# MI.net
KiCad netlist of a schematic drawn in Altium Designer
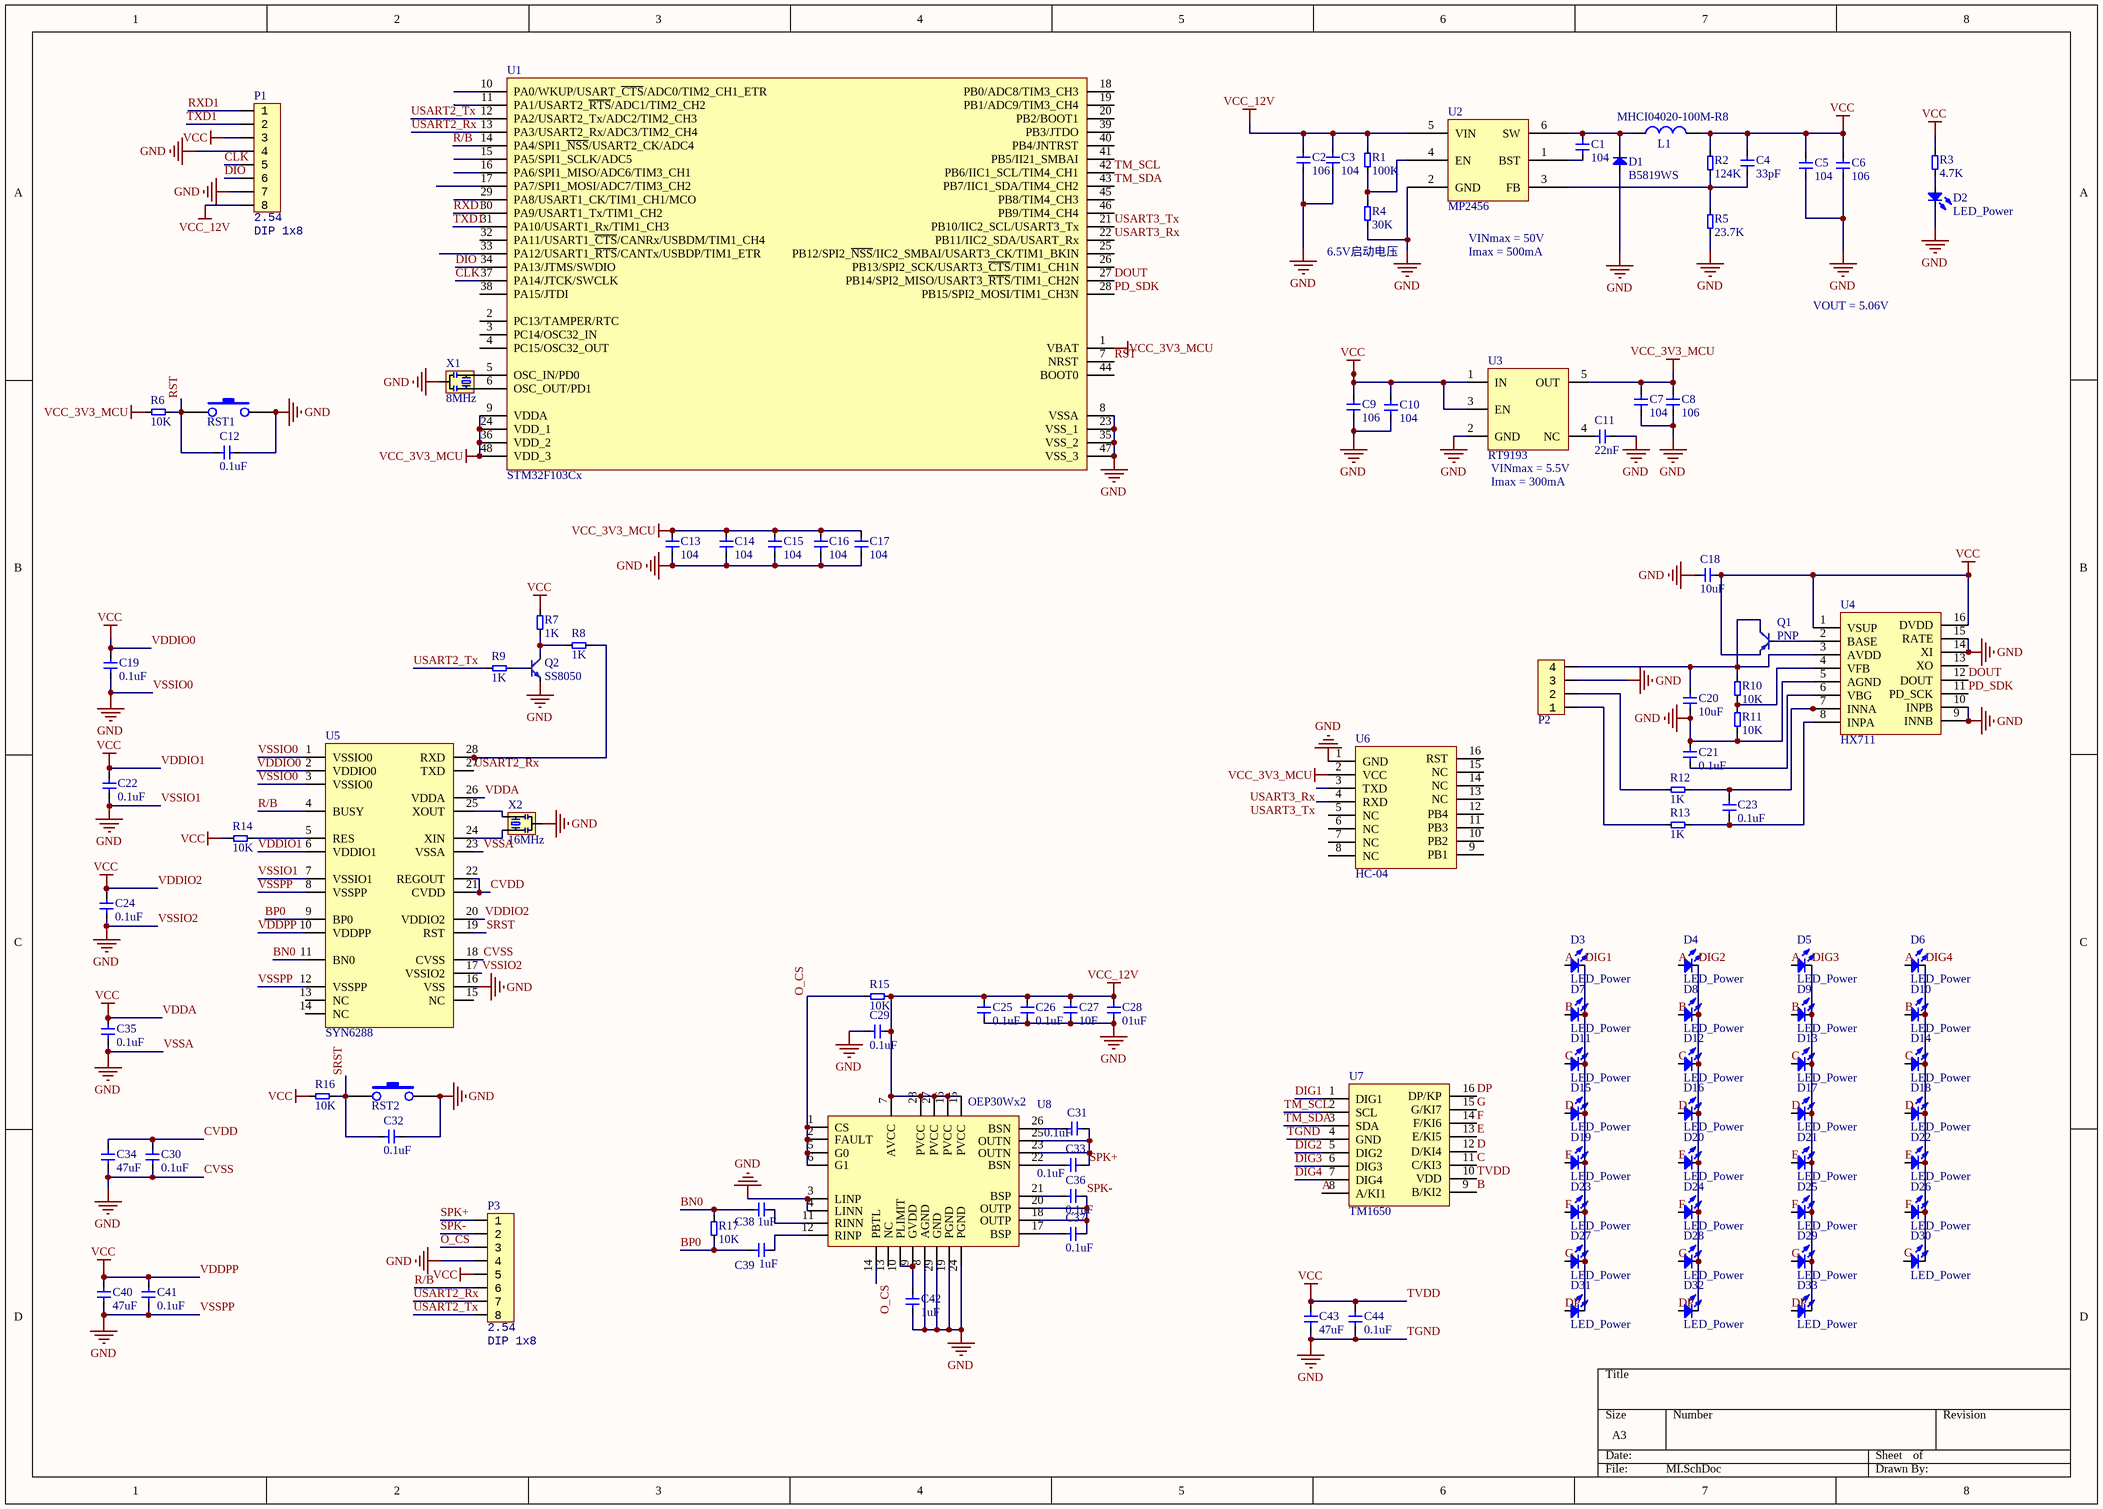
[diagram p0: MI.SchDoc]

(export (version "E")
  (design (tool "Eeschema 10.0.6"))
  (components
    (comp (ref "C1") (value "104") (footprint "CAP-0603-L") (libsource (lib "Hare_Library") (part "CAP")))
    (comp (ref "C2") (value "106") (footprint "CAP-0603-L") (libsource (lib "Hare_Library") (part "CAP")))
    (comp (ref "C3") (value "104") (footprint "CAP-0603-L") (libsource (lib "Hare_Library") (part "CAP")))
    (comp (ref "C4") (value "33pF") (footprint "CAP-0603-L") (libsource (lib "Hare_Library") (part "CAP")))
    (comp (ref "C5") (value "104") (footprint "CAP-0603-L") (libsource (lib "Hare_Library") (part "CAP")))
    (comp (ref "C6") (value "106") (footprint "CAP-0603-L") (libsource (lib "Hare_Library") (part "CAP")))
    (comp (ref "C7") (value "104") (footprint "CAP-0603-L") (libsource (lib "Hare_Library") (part "CAP")))
    (comp (ref "C8") (value "106") (footprint "CAP-0603-L") (libsource (lib "Hare_Library") (part "CAP")))
    (comp (ref "C9") (value "106") (footprint "CAP-0603-L") (libsource (lib "Hare_Library") (part "CAP")))
    (comp (ref "C10") (value "104") (footprint "CAP-0603-L") (libsource (lib "Hare_Library") (part "CAP")))
    (comp (ref "C11") (value "22nF") (footprint "CAP-0603-L") (libsource (lib "Hare_Library") (part "CAP")))
    (comp (ref "C12")
      (value "0.1uF")
      (footprint "CAP-0603-L")
      (libsource (lib "DaqoLib_Devices") (part "CAP"))
    )
    (comp (ref "C13") (value "104") (footprint "CAP-0603-L") (libsource (lib "DaqoLib_Devices") (part "CAP")))
    (comp (ref "C14") (value "104") (footprint "CAP-0603-L") (libsource (lib "DaqoLib_Devices") (part "CAP")))
    (comp (ref "C15") (value "104") (footprint "CAP-0603-L") (libsource (lib "DaqoLib_Devices") (part "CAP")))
    (comp (ref "C16") (value "104") (footprint "CAP-0603-L") (libsource (lib "DaqoLib_Devices") (part "CAP")))
    (comp (ref "C17") (value "104") (footprint "CAP-0603-L") (libsource (lib "DaqoLib_Devices") (part "CAP")))
    (comp (ref "C18")
      (value "10uF")
      (footprint "CAP-0603-L")
      (libsource (lib "DaqoLib_Devices") (part "CAP"))
    )
    (comp (ref "C19")
      (value "0.1uF")
      (footprint "CAP-0603-L")
      (libsource (lib "DaqoLib_Devices") (part "CAP"))
    )
    (comp (ref "C20")
      (value "10uF")
      (footprint "CAP-0603-L")
      (libsource (lib "DaqoLib_Devices") (part "CAP"))
    )
    (comp (ref "C21")
      (value "0.1uF")
      (footprint "CAP-0603-L")
      (libsource (lib "DaqoLib_Devices") (part "CAP"))
    )
    (comp (ref "C22")
      (value "0.1uF")
      (footprint "CAP-0603-L")
      (libsource (lib "DaqoLib_Devices") (part "CAP"))
    )
    (comp (ref "C23")
      (value "0.1uF")
      (footprint "CAP-0603-L")
      (libsource (lib "DaqoLib_Devices") (part "CAP"))
    )
    (comp (ref "C24")
      (value "0.1uF")
      (footprint "CAP-0603-L")
      (libsource (lib "DaqoLib_Devices") (part "CAP"))
    )
    (comp (ref "C25")
      (value "0.1uF")
      (footprint "CAP-0603-L")
      (libsource (lib "DaqoLib_Devices") (part "CAP"))
    )
    (comp (ref "C26")
      (value "0.1uF")
      (footprint "CAP-0603-L")
      (libsource (lib "DaqoLib_Devices") (part "CAP"))
    )
    (comp (ref "C27") (value "10F") (footprint "CAP-0603-L") (libsource (lib "DaqoLib_Devices") (part "CAP")))
    (comp (ref "C28")
      (value "01uF")
      (footprint "CAP-0603-L")
      (libsource (lib "DaqoLib_Devices") (part "CAP"))
    )
    (comp (ref "C29")
      (value "0.1uF")
      (footprint "CAP-0603-L")
      (libsource (lib "DaqoLib_Devices") (part "CAP"))
    )
    (comp (ref "C30")
      (value "0.1uF")
      (footprint "CAP-0603-L")
      (libsource (lib "DaqoLib_Devices") (part "CAP"))
    )
    (comp (ref "C31")
      (value "0.1uF")
      (footprint "CAP-0603-L")
      (libsource (lib "DaqoLib_Devices") (part "CAP"))
    )
    (comp (ref "C32")
      (value "0.1uF")
      (footprint "CAP-0603-L")
      (libsource (lib "DaqoLib_Devices") (part "CAP"))
    )
    (comp (ref "C33")
      (value "0.1uF")
      (footprint "CAP-0603-L")
      (libsource (lib "DaqoLib_Devices") (part "CAP"))
    )
    (comp (ref "C34")
      (value "47uF")
      (footprint "CAP-0603-L")
      (libsource (lib "DaqoLib_Devices") (part "CAP"))
    )
    (comp (ref "C35")
      (value "0.1uF")
      (footprint "CAP-0603-L")
      (libsource (lib "DaqoLib_Devices") (part "CAP"))
    )
    (comp (ref "C36")
      (value "0.1uF")
      (footprint "CAP-0603-L")
      (libsource (lib "DaqoLib_Devices") (part "CAP"))
    )
    (comp (ref "C37")
      (value "0.1uF")
      (footprint "CAP-0603-L")
      (libsource (lib "DaqoLib_Devices") (part "CAP"))
    )
    (comp (ref "C38") (value "1uF") (footprint "CAP-0603-L") (libsource (lib "DaqoLib_Devices") (part "CAP")))
    (comp (ref "C39") (value "1uF") (footprint "CAP-0603-L") (libsource (lib "DaqoLib_Devices") (part "CAP")))
    (comp (ref "C40")
      (value "47uF")
      (footprint "CAP-0603-L")
      (libsource (lib "DaqoLib_Devices") (part "CAP"))
    )
    (comp (ref "C41")
      (value "0.1uF")
      (footprint "CAP-0603-L")
      (libsource (lib "DaqoLib_Devices") (part "CAP"))
    )
    (comp (ref "C42") (value "1uF") (footprint "CAP-0603-L") (libsource (lib "DaqoLib_Devices") (part "CAP")))
    (comp (ref "C43")
      (value "47uF")
      (footprint "CAP-0603-L")
      (libsource (lib "DaqoLib_Devices") (part "CAP"))
    )
    (comp (ref "C44")
      (value "0.1uF")
      (footprint "CAP-0603-L")
      (libsource (lib "DaqoLib_Devices") (part "CAP"))
    )
    (comp (ref "D1") (value "B5819WS") (footprint "SOD_323") (libsource (lib "Hare_Library") (part "Diode")))
    (comp (ref "D2")
      (value "LED_Power")
      (footprint "LED_0603-L")
      (libsource (lib "Hare_Library") (part "LED"))
    )
    (comp (ref "D3")
      (value "LED_Power")
      (footprint "LED_0603-L")
      (libsource (lib "Hare_Library") (part "LED"))
    )
    (comp (ref "D4")
      (value "LED_Power")
      (footprint "LED_0603-L")
      (libsource (lib "Hare_Library") (part "LED"))
    )
    (comp (ref "D5")
      (value "LED_Power")
      (footprint "LED_0603-L")
      (libsource (lib "Hare_Library") (part "LED"))
    )
    (comp (ref "D6")
      (value "LED_Power")
      (footprint "LED_0603-L")
      (libsource (lib "Hare_Library") (part "LED"))
    )
    (comp (ref "D7")
      (value "LED_Power")
      (footprint "LED_0603-L")
      (libsource (lib "Hare_Library") (part "LED"))
    )
    (comp (ref "D8")
      (value "LED_Power")
      (footprint "LED_0603-L")
      (libsource (lib "Hare_Library") (part "LED"))
    )
    (comp (ref "D9")
      (value "LED_Power")
      (footprint "LED_0603-L")
      (libsource (lib "Hare_Library") (part "LED"))
    )
    (comp (ref "D10")
      (value "LED_Power")
      (footprint "LED_0603-L")
      (libsource (lib "Hare_Library") (part "LED"))
    )
    (comp (ref "D11")
      (value "LED_Power")
      (footprint "LED_0603-L")
      (libsource (lib "Hare_Library") (part "LED"))
    )
    (comp (ref "D12")
      (value "LED_Power")
      (footprint "LED_0603-L")
      (libsource (lib "Hare_Library") (part "LED"))
    )
    (comp (ref "D13")
      (value "LED_Power")
      (footprint "LED_0603-L")
      (libsource (lib "Hare_Library") (part "LED"))
    )
    (comp (ref "D14")
      (value "LED_Power")
      (footprint "LED_0603-L")
      (libsource (lib "Hare_Library") (part "LED"))
    )
    (comp (ref "D15")
      (value "LED_Power")
      (footprint "LED_0603-L")
      (libsource (lib "Hare_Library") (part "LED"))
    )
    (comp (ref "D16")
      (value "LED_Power")
      (footprint "LED_0603-L")
      (libsource (lib "Hare_Library") (part "LED"))
    )
    (comp (ref "D17")
      (value "LED_Power")
      (footprint "LED_0603-L")
      (libsource (lib "Hare_Library") (part "LED"))
    )
    (comp (ref "D18")
      (value "LED_Power")
      (footprint "LED_0603-L")
      (libsource (lib "Hare_Library") (part "LED"))
    )
    (comp (ref "D19")
      (value "LED_Power")
      (footprint "LED_0603-L")
      (libsource (lib "Hare_Library") (part "LED"))
    )
    (comp (ref "D20")
      (value "LED_Power")
      (footprint "LED_0603-L")
      (libsource (lib "Hare_Library") (part "LED"))
    )
    (comp (ref "D21")
      (value "LED_Power")
      (footprint "LED_0603-L")
      (libsource (lib "Hare_Library") (part "LED"))
    )
    (comp (ref "D22")
      (value "LED_Power")
      (footprint "LED_0603-L")
      (libsource (lib "Hare_Library") (part "LED"))
    )
    (comp (ref "D23")
      (value "LED_Power")
      (footprint "LED_0603-L")
      (libsource (lib "Hare_Library") (part "LED"))
    )
    (comp (ref "D24")
      (value "LED_Power")
      (footprint "LED_0603-L")
      (libsource (lib "Hare_Library") (part "LED"))
    )
    (comp (ref "D25")
      (value "LED_Power")
      (footprint "LED_0603-L")
      (libsource (lib "Hare_Library") (part "LED"))
    )
    (comp (ref "D26")
      (value "LED_Power")
      (footprint "LED_0603-L")
      (libsource (lib "Hare_Library") (part "LED"))
    )
    (comp (ref "D27")
      (value "LED_Power")
      (footprint "LED_0603-L")
      (libsource (lib "Hare_Library") (part "LED"))
    )
    (comp (ref "D28")
      (value "LED_Power")
      (footprint "LED_0603-L")
      (libsource (lib "Hare_Library") (part "LED"))
    )
    (comp (ref "D29")
      (value "LED_Power")
      (footprint "LED_0603-L")
      (libsource (lib "Hare_Library") (part "LED"))
    )
    (comp (ref "D30")
      (value "LED_Power")
      (footprint "LED_0603-L")
      (libsource (lib "Hare_Library") (part "LED"))
    )
    (comp (ref "D31")
      (value "LED_Power")
      (footprint "LED_0603-L")
      (libsource (lib "Hare_Library") (part "LED"))
    )
    (comp (ref "D32")
      (value "LED_Power")
      (footprint "LED_0603-L")
      (libsource (lib "Hare_Library") (part "LED"))
    )
    (comp (ref "D33")
      (value "LED_Power")
      (footprint "LED_0603-L")
      (libsource (lib "Hare_Library") (part "LED"))
    )
    (comp (ref "L1")
      (value "MHCI04020-100M-R8")
      (footprint "L-0420")
      (description "电感")
      (libsource (lib "Hare_Library") (part "Inductor"))
    )
    (comp (ref "P1")
      (value "2.54")
      (footprint "HDR1X8_2.54_180")
      (description "Header")
      (fields (field (name "TYPE") "DIP 1x8") (field (name "Comment") "DIP 1x8"))
      (libsource (lib "DaqoLib_Connectors") (part "HDR1x8_2.54"))
    )
    (comp (ref "P2")
      (value "HDR1x4_2.54")
      (footprint "HDR1X4_2.54_180")
      (description "Header")
      (libsource (lib "DaqoLib_Connectors") (part "HDR1x4_2.54"))
    )
    (comp (ref "P3")
      (value "2.54")
      (footprint "HDR1X8_2.54_180")
      (description "Header")
      (fields (field (name "TYPE") "DIP 1x8") (field (name "Comment") "DIP 1x8"))
      (libsource (lib "DaqoLib_Connectors") (part "HDR1x8_2.54"))
    )
    (comp (ref "Q1")
      (value "PNP")
      (footprint "SOT-23-3")
      (description "Transistor")
      (libsource (lib "DaqoLib_Devices") (part "BJT_PNP"))
    )
    (comp (ref "Q2")
      (value "SS8050")
      (footprint "SOT-23-3")
      (description "Transistor")
      (libsource (lib "DaqoLib_Devices") (part "BJT_NPN"))
    )
    (comp (ref "R1") (value "100K") (footprint "R-0603-L") (libsource (lib "Hare_Library") (part "Res")))
    (comp (ref "R2") (value "124K") (footprint "R-0603-L") (libsource (lib "Hare_Library") (part "Res")))
    (comp (ref "R3") (value "4.7K") (footprint "R-0603-L") (libsource (lib "Hare_Library") (part "Res")))
    (comp (ref "R4") (value "30K") (footprint "R-0603-L") (libsource (lib "Hare_Library") (part "Res")))
    (comp (ref "R5") (value "23.7K") (footprint "R-0603-L") (libsource (lib "Hare_Library") (part "Res")))
    (comp (ref "R6") (value "10K") (footprint "R-0603-L") (libsource (lib "DaqoLib_Devices") (part "Res")))
    (comp (ref "R7") (value "1K") (footprint "R-0603-L") (libsource (lib "DaqoLib_Devices") (part "Res")))
    (comp (ref "R8") (value "1K") (footprint "R-0603-L") (libsource (lib "DaqoLib_Devices") (part "Res")))
    (comp (ref "R9") (value "1K") (footprint "R-0603-L") (libsource (lib "DaqoLib_Devices") (part "Res")))
    (comp (ref "R10") (value "10K") (footprint "R-0603-L") (libsource (lib "DaqoLib_Devices") (part "Res")))
    (comp (ref "R11") (value "10K") (footprint "R-0603-L") (libsource (lib "DaqoLib_Devices") (part "Res")))
    (comp (ref "R12") (value "1K") (footprint "R-0603-L") (libsource (lib "DaqoLib_Devices") (part "Res")))
    (comp (ref "R13") (value "1K") (footprint "R-0603-L") (libsource (lib "DaqoLib_Devices") (part "Res")))
    (comp (ref "R14") (value "10K") (footprint "R-0603-L") (libsource (lib "DaqoLib_Devices") (part "Res")))
    (comp (ref "R15") (value "10K") (footprint "R-0603-L") (libsource (lib "DaqoLib_Devices") (part "Res")))
    (comp (ref "R16") (value "10K") (footprint "R-0603-L") (libsource (lib "DaqoLib_Devices") (part "Res")))
    (comp (ref "R17") (value "10K") (footprint "R-0603-L") (libsource (lib "DaqoLib_Devices") (part "Res")))
    (comp (ref "RST1") (value "按键") (footprint "KEY_2S") (libsource (lib "DaqoLib_Devices") (part "按键")))
    (comp (ref "RST2") (value "按键") (footprint "KEY_2S") (libsource (lib "DaqoLib_Devices") (part "按键")))
    (comp (ref "U1")
      (value "STM32F103Cx")
      (footprint "LQFP_48")
      (libsource (lib "DaqoLib_IC") (part "STM32F103Cx"))
    )
    (comp (ref "U2") (value "MP2456") (footprint "SOT-23-6") (libsource (lib "DriveMixed") (part "MP2451")))
    (comp (ref "U3")
      (value "RT9193")
      (footprint "SOT-23-5")
      (libsource (lib "Hare_Library") (part "LP5907MFX"))
    )
    (comp (ref "U4") (value "HX711") (footprint "SOP_E150_16") (libsource (lib "DaqoLib_IC") (part "HX711")))
    (comp (ref "U5")
      (value "SYN6288")
      (footprint "SSOP28-26-209")
      (libsource (lib "DaqoLib_IC") (part "SYN6288"))
    )
    (comp (ref "U6") (value "HC-04") (footprint "HC-25") (libsource (lib "DaqoLib_IC") (part "HC-04")))
    (comp (ref "U7")
      (value "TM1650")
      (footprint "SOP_E150_16")
      (libsource (lib "DaqoLib_IC") (part "TM1650"))
    )
    (comp (ref "U8")
      (value "OEP30Wx2")
      (footprint "TSSOP_E170_P0.65_28_PAD")
      (libsource (lib "DaqoLib_IC") (part "OEP30Wx2"))
    )
    (comp (ref "X1") (value "8MHz") (footprint "XTAL-3213-3") (libsource (lib "") (part "XTAL-3215-3_1")))
    (comp (ref "X2")
      (value "16MHz")
      (footprint "XTAL-3213-3")
      (libsource (lib "DaqoLib_Devices") (part "XTAL-3215-3"))
    )
  )
  (nets
    (net (code "1") (name "/A") (class "Default")
      (node (ref "D3") (pin "1") (pinfunction "1_1") (pintype "passive"))
      (node (ref "D4") (pin "1") (pinfunction "1_1") (pintype "passive"))
      (node (ref "D5") (pin "1") (pinfunction "1_1") (pintype "passive"))
      (node (ref "D6") (pin "1") (pinfunction "1_1") (pintype "passive"))
      (node (ref "U7") (pin "8") (pinfunction "A/KI1_8") (pintype "passive"))
    )
    (net (code "2") (name "/B") (class "Default")
      (node (ref "D10") (pin "1") (pinfunction "1_1") (pintype "passive"))
      (node (ref "D7") (pin "1") (pinfunction "1_1") (pintype "passive"))
      (node (ref "D8") (pin "1") (pinfunction "1_1") (pintype "passive"))
      (node (ref "D9") (pin "1") (pinfunction "1_1") (pintype "passive"))
      (node (ref "U7") (pin "9") (pinfunction "B/KI2_9") (pintype "passive"))
    )
    (net (code "3") (name "/BN0") (class "Default")
      (node (ref "C38") (pin "2") (pinfunction "2_2") (pintype "passive"))
      (node (ref "R17") (pin "2") (pinfunction "2_2") (pintype "passive"))
      (node (ref "U5") (pin "11") (pinfunction "BN0_11") (pintype "passive"))
    )
    (net (code "4") (name "/BP0") (class "Default")
      (node (ref "C39") (pin "2") (pinfunction "2_2") (pintype "passive"))
      (node (ref "R17") (pin "1") (pinfunction "1_1") (pintype "passive"))
      (node (ref "U5") (pin "9") (pinfunction "BP0_9") (pintype "passive"))
    )
    (net (code "5") (name "/C") (class "Default")
      (node (ref "D11") (pin "1") (pinfunction "1_1") (pintype "passive"))
      (node (ref "D12") (pin "1") (pinfunction "1_1") (pintype "passive"))
      (node (ref "D13") (pin "1") (pinfunction "1_1") (pintype "passive"))
      (node (ref "D14") (pin "1") (pinfunction "1_1") (pintype "passive"))
      (node (ref "U7") (pin "11") (pinfunction "C/KI3_11") (pintype "passive"))
    )
    (net (code "6") (name "/CLK") (class "Default")
      (node (ref "P1") (pin "5") (pinfunction "5_5") (pintype "passive"))
      (node (ref "U1") (pin "37") (pinfunction "PA14/JTCK/SWCLK_37") (pintype "passive"))
    )
    (net (code "7") (name "/CVDD") (class "Default")
      (node (ref "C30") (pin "1") (pinfunction "1_1") (pintype "passive"))
      (node (ref "C34") (pin "1") (pinfunction "1_1") (pintype "passive"))
      (node (ref "U5") (pin "21") (pinfunction "CVDD_21") (pintype "passive"))
      (node (ref "U5") (pin "22") (pinfunction "REGOUT_22") (pintype "passive"))
    )
    (net (code "8") (name "/D") (class "Default")
      (node (ref "D15") (pin "1") (pinfunction "1_1") (pintype "passive"))
      (node (ref "D16") (pin "1") (pinfunction "1_1") (pintype "passive"))
      (node (ref "D17") (pin "1") (pinfunction "1_1") (pintype "passive"))
      (node (ref "D18") (pin "1") (pinfunction "1_1") (pintype "passive"))
      (node (ref "U7") (pin "12") (pinfunction "D/KI4_12") (pintype "passive"))
    )
    (net (code "9") (name "/DIG1") (class "Default")
      (node (ref "D11") (pin "2") (pinfunction "2_2") (pintype "passive"))
      (node (ref "D15") (pin "2") (pinfunction "2_2") (pintype "passive"))
      (node (ref "D19") (pin "2") (pinfunction "2_2") (pintype "passive"))
      (node (ref "D23") (pin "2") (pinfunction "2_2") (pintype "passive"))
      (node (ref "D27") (pin "2") (pinfunction "2_2") (pintype "passive"))
      (node (ref "D3") (pin "2") (pinfunction "2_2") (pintype "passive"))
      (node (ref "D31") (pin "2") (pinfunction "2_2") (pintype "passive"))
      (node (ref "D7") (pin "2") (pinfunction "2_2") (pintype "passive"))
      (node (ref "U7") (pin "1") (pinfunction "DIG1_1") (pintype "passive"))
    )
    (net (code "10") (name "/DIG2") (class "Default")
      (node (ref "D12") (pin "2") (pinfunction "2_2") (pintype "passive"))
      (node (ref "D16") (pin "2") (pinfunction "2_2") (pintype "passive"))
      (node (ref "D20") (pin "2") (pinfunction "2_2") (pintype "passive"))
      (node (ref "D24") (pin "2") (pinfunction "2_2") (pintype "passive"))
      (node (ref "D28") (pin "2") (pinfunction "2_2") (pintype "passive"))
      (node (ref "D32") (pin "2") (pinfunction "2_2") (pintype "passive"))
      (node (ref "D4") (pin "2") (pinfunction "2_2") (pintype "passive"))
      (node (ref "D8") (pin "2") (pinfunction "2_2") (pintype "passive"))
      (node (ref "U7") (pin "5") (pinfunction "DIG2_5") (pintype "passive"))
    )
    (net (code "11") (name "/DIG3") (class "Default")
      (node (ref "D13") (pin "2") (pinfunction "2_2") (pintype "passive"))
      (node (ref "D17") (pin "2") (pinfunction "2_2") (pintype "passive"))
      (node (ref "D21") (pin "2") (pinfunction "2_2") (pintype "passive"))
      (node (ref "D25") (pin "2") (pinfunction "2_2") (pintype "passive"))
      (node (ref "D29") (pin "2") (pinfunction "2_2") (pintype "passive"))
      (node (ref "D33") (pin "2") (pinfunction "2_2") (pintype "passive"))
      (node (ref "D5") (pin "2") (pinfunction "2_2") (pintype "passive"))
      (node (ref "D9") (pin "2") (pinfunction "2_2") (pintype "passive"))
      (node (ref "U7") (pin "6") (pinfunction "DIG3_6") (pintype "passive"))
    )
    (net (code "12") (name "/DIG4") (class "Default")
      (node (ref "D10") (pin "2") (pinfunction "2_2") (pintype "passive"))
      (node (ref "D14") (pin "2") (pinfunction "2_2") (pintype "passive"))
      (node (ref "D18") (pin "2") (pinfunction "2_2") (pintype "passive"))
      (node (ref "D22") (pin "2") (pinfunction "2_2") (pintype "passive"))
      (node (ref "D26") (pin "2") (pinfunction "2_2") (pintype "passive"))
      (node (ref "D30") (pin "2") (pinfunction "2_2") (pintype "passive"))
      (node (ref "D6") (pin "2") (pinfunction "2_2") (pintype "passive"))
      (node (ref "U7") (pin "7") (pinfunction "DIG4_7") (pintype "passive"))
    )
    (net (code "13") (name "/DIO") (class "Default")
      (node (ref "P1") (pin "6") (pinfunction "6_6") (pintype "passive"))
      (node (ref "U1") (pin "34") (pinfunction "PA13/JTMS/SWDIO_34") (pintype "passive"))
    )
    (net (code "14") (name "/DOUT") (class "Default")
      (node (ref "U1") (pin "27") (pinfunction "PB14/SPI2_MISO/USART3_~{RTS}/TIM1_CH2N_27") (pintype "passive"))
      (node (ref "U4") (pin "12") (pinfunction "DOUT_12") (pintype "passive"))
    )
    (net (code "15") (name "/DP") (class "Default")
      (node (ref "D31") (pin "1") (pinfunction "1_1") (pintype "passive"))
      (node (ref "D32") (pin "1") (pinfunction "1_1") (pintype "passive"))
      (node (ref "D33") (pin "1") (pinfunction "1_1") (pintype "passive"))
      (node (ref "U7") (pin "16") (pinfunction "DP/KP_16") (pintype "passive"))
    )
    (net (code "16") (name "/E") (class "Default")
      (node (ref "D19") (pin "1") (pinfunction "1_1") (pintype "passive"))
      (node (ref "D20") (pin "1") (pinfunction "1_1") (pintype "passive"))
      (node (ref "D21") (pin "1") (pinfunction "1_1") (pintype "passive"))
      (node (ref "D22") (pin "1") (pinfunction "1_1") (pintype "passive"))
      (node (ref "U7") (pin "13") (pinfunction "E/KI5_13") (pintype "passive"))
    )
    (net (code "17") (name "/F") (class "Default")
      (node (ref "D23") (pin "1") (pinfunction "1_1") (pintype "passive"))
      (node (ref "D24") (pin "1") (pinfunction "1_1") (pintype "passive"))
      (node (ref "D25") (pin "1") (pinfunction "1_1") (pintype "passive"))
      (node (ref "D26") (pin "1") (pinfunction "1_1") (pintype "passive"))
      (node (ref "U7") (pin "14") (pinfunction "F/KI6_14") (pintype "passive"))
    )
    (net (code "18") (name "/G") (class "Default")
      (node (ref "D27") (pin "1") (pinfunction "1_1") (pintype "passive"))
      (node (ref "D28") (pin "1") (pinfunction "1_1") (pintype "passive"))
      (node (ref "D29") (pin "1") (pinfunction "1_1") (pintype "passive"))
      (node (ref "D30") (pin "1") (pinfunction "1_1") (pintype "passive"))
      (node (ref "U7") (pin "15") (pinfunction "G/KI7_15") (pintype "passive"))
    )
    (net (code "19") (name "/O_CS") (class "Default")
      (node (ref "P3") (pin "3") (pinfunction "3_3") (pintype "passive"))
      (node (ref "R15") (pin "1") (pinfunction "1_1") (pintype "passive"))
      (node (ref "U8") (pin "1") (pinfunction "CS_1") (pintype "passive"))
      (node (ref "U8") (pin "14") (pinfunction "PBTL_14") (pintype "passive"))
      (node (ref "U8") (pin "2") (pinfunction "FAULT_2") (pintype "passive"))
      (node (ref "U8") (pin "5") (pinfunction "G0_5") (pintype "passive"))
      (node (ref "U8") (pin "6") (pinfunction "G1_6") (pintype "passive"))
    )
    (net (code "20") (name "/PD_SDK") (class "Default")
      (node (ref "U1") (pin "28") (pinfunction "PB15/SPI2_MOSI/TIM1_CH3N_28") (pintype "passive"))
      (node (ref "U4") (pin "11") (pinfunction "PD_SCK_11") (pintype "passive"))
    )
    (net (code "21") (name "/RST") (class "Default")
      (node (ref "C12") (pin "1") (pinfunction "1_1") (pintype "passive"))
      (node (ref "R6") (pin "2") (pinfunction "2_2") (pintype "passive"))
      (node (ref "RST1") (pin "1") (pinfunction "1_1") (pintype "passive"))
      (node (ref "U1") (pin "7") (pinfunction "NRST_7") (pintype "passive"))
    )
    (net (code "22") (name "/RXD1") (class "Default")
      (node (ref "P1") (pin "1") (pinfunction "1_1") (pintype "passive"))
      (node (ref "U1") (pin "30") (pinfunction "PA9/USART1_Tx/TIM1_CH2_30") (pintype "passive"))
    )
    (net (code "23") (name "/R{slash}B") (class "Default")
      (node (ref "P3") (pin "6") (pinfunction "6_6") (pintype "passive"))
      (node (ref "U1") (pin "14") (pinfunction "PA4/SPI1_~{NSS}/USART2_CK/ADC4_14") (pintype "passive"))
      (node (ref "U5") (pin "4") (pinfunction "BUSY_4") (pintype "passive"))
    )
    (net (code "24") (name "/SPK+") (class "Default")
      (node (ref "C31") (pin "2") (pinfunction "2_2") (pintype "passive"))
      (node (ref "C33") (pin "2") (pinfunction "2_2") (pintype "passive"))
      (node (ref "P3") (pin "1") (pinfunction "1_1") (pintype "passive"))
      (node (ref "U8") (pin "23") (pinfunction "OUTN_23") (pintype "passive"))
      (node (ref "U8") (pin "25") (pinfunction "OUTN_25") (pintype "passive"))
    )
    (net (code "25") (name "/SPK-") (class "Default")
      (node (ref "C36") (pin "2") (pinfunction "2_2") (pintype "passive"))
      (node (ref "C37") (pin "2") (pinfunction "2_2") (pintype "passive"))
      (node (ref "P3") (pin "2") (pinfunction "2_2") (pintype "passive"))
      (node (ref "U8") (pin "18") (pinfunction "OUTP_18") (pintype "passive"))
      (node (ref "U8") (pin "20") (pinfunction "OUTP_20") (pintype "passive"))
    )
    (net (code "26") (name "/SRST") (class "Default")
      (node (ref "C32") (pin "1") (pinfunction "1_1") (pintype "passive"))
      (node (ref "R16") (pin "2") (pinfunction "2_2") (pintype "passive"))
      (node (ref "RST2") (pin "1") (pinfunction "1_1") (pintype "passive"))
      (node (ref "U5") (pin "19") (pinfunction "RST_19") (pintype "passive"))
    )
    (net (code "27") (name "/TM_SCL") (class "Default")
      (node (ref "U1") (pin "42") (pinfunction "PB6/IIC1_SCL/TIM4_CH1_42") (pintype "passive"))
      (node (ref "U7") (pin "2") (pinfunction "SCL_2") (pintype "passive"))
    )
    (net (code "28") (name "/TM_SDA") (class "Default")
      (node (ref "U1") (pin "43") (pinfunction "PB7/IIC1_SDA/TIM4_CH2_43") (pintype "passive"))
      (node (ref "U7") (pin "3") (pinfunction "SDA_3") (pintype "passive"))
    )
    (net (code "29") (name "/TXD1") (class "Default")
      (node (ref "P1") (pin "2") (pinfunction "2_2") (pintype "passive"))
      (node (ref "U1") (pin "31") (pinfunction "PA10/USART1_Rx/TIM1_CH3_31") (pintype "passive"))
    )
    (net (code "30") (name "/USART2_Rx") (class "Default")
      (node (ref "P3") (pin "7") (pinfunction "7_7") (pintype "passive"))
      (node (ref "U1") (pin "13") (pinfunction "PA3/USART2_Rx/ADC3/TIM2_CH4_13") (pintype "passive"))
      (node (ref "U5") (pin "27") (pinfunction "TXD_27") (pintype "passive"))
    )
    (net (code "31") (name "/USART2_Tx") (class "Default")
      (node (ref "P3") (pin "8") (pinfunction "8_8") (pintype "passive"))
      (node (ref "R9") (pin "2") (pinfunction "2_2") (pintype "passive"))
      (node (ref "U1") (pin "12") (pinfunction "PA2/USART2_Tx/ADC2/TIM2_CH3_12") (pintype "passive"))
    )
    (net (code "32") (name "/USART3_Rx") (class "Default")
      (node (ref "U1") (pin "22") (pinfunction "PB11/IIC2_SDA/USART_Rx_22") (pintype "passive"))
      (node (ref "U6") (pin "3") (pinfunction "TXD_3") (pintype "passive"))
    )
    (net (code "33") (name "/USART3_Tx") (class "Default")
      (node (ref "U1") (pin "21") (pinfunction "PB10/IIC2_SCL/USART3_Tx_21") (pintype "passive"))
      (node (ref "U6") (pin "4") (pinfunction "RXD_4") (pintype "passive"))
    )
    (net (code "34") (name "GND") (class "Default")
      (node (ref "C10") (pin "1") (pinfunction "1_1") (pintype "passive"))
      (node (ref "C11") (pin "2") (pinfunction "2_2") (pintype "passive"))
      (node (ref "C12") (pin "2") (pinfunction "2_2") (pintype "passive"))
      (node (ref "C13") (pin "2") (pinfunction "2_2") (pintype "passive"))
      (node (ref "C14") (pin "2") (pinfunction "2_2") (pintype "passive"))
      (node (ref "C15") (pin "2") (pinfunction "2_2") (pintype "passive"))
      (node (ref "C16") (pin "2") (pinfunction "2_2") (pintype "passive"))
      (node (ref "C17") (pin "2") (pinfunction "2_2") (pintype "passive"))
      (node (ref "C18") (pin "1") (pinfunction "1_1") (pintype "passive"))
      (node (ref "C19") (pin "2") (pinfunction "2_2") (pintype "passive"))
      (node (ref "C2") (pin "1") (pinfunction "1_1") (pintype "passive"))
      (node (ref "C20") (pin "1") (pinfunction "1_1") (pintype "passive"))
      (node (ref "C21") (pin "2") (pinfunction "2_2") (pintype "passive"))
      (node (ref "C22") (pin "2") (pinfunction "2_2") (pintype "passive"))
      (node (ref "C24") (pin "2") (pinfunction "2_2") (pintype "passive"))
      (node (ref "C25") (pin "2") (pinfunction "2_2") (pintype "passive"))
      (node (ref "C26") (pin "2") (pinfunction "2_2") (pintype "passive"))
      (node (ref "C27") (pin "2") (pinfunction "2_2") (pintype "passive"))
      (node (ref "C28") (pin "2") (pinfunction "2_2") (pintype "passive"))
      (node (ref "C29") (pin "1") (pinfunction "1_1") (pintype "passive"))
      (node (ref "C3") (pin "1") (pinfunction "1_1") (pintype "passive"))
      (node (ref "C30") (pin "2") (pinfunction "2_2") (pintype "passive"))
      (node (ref "C32") (pin "2") (pinfunction "2_2") (pintype "passive"))
      (node (ref "C34") (pin "2") (pinfunction "2_2") (pintype "passive"))
      (node (ref "C35") (pin "2") (pinfunction "2_2") (pintype "passive"))
      (node (ref "C40") (pin "2") (pinfunction "2_2") (pintype "passive"))
      (node (ref "C41") (pin "2") (pinfunction "2_2") (pintype "passive"))
      (node (ref "C42") (pin "1") (pinfunction "1_1") (pintype "passive"))
      (node (ref "C43") (pin "2") (pinfunction "2_2") (pintype "passive"))
      (node (ref "C44") (pin "2") (pinfunction "2_2") (pintype "passive"))
      (node (ref "C5") (pin "1") (pinfunction "1_1") (pintype "passive"))
      (node (ref "C6") (pin "1") (pinfunction "1_1") (pintype "passive"))
      (node (ref "C7") (pin "2") (pinfunction "2_2") (pintype "passive"))
      (node (ref "C8") (pin "1") (pinfunction "1_1") (pintype "passive"))
      (node (ref "C9") (pin "1") (pinfunction "1_1") (pintype "passive"))
      (node (ref "D1") (pin "1") (pinfunction "1_1") (pintype "passive"))
      (node (ref "D2") (pin "2") (pinfunction "2_2") (pintype "passive"))
      (node (ref "P1") (pin "4") (pinfunction "4_4") (pintype "passive"))
      (node (ref "P1") (pin "7") (pinfunction "7_7") (pintype "passive"))
      (node (ref "P2") (pin "3") (pinfunction "3_3") (pintype "passive"))
      (node (ref "P3") (pin "4") (pinfunction "4_4") (pintype "passive"))
      (node (ref "Q2") (pin "2") (pinfunction "E_2") (pintype "passive"))
      (node (ref "R11") (pin "1") (pinfunction "1_1") (pintype "passive"))
      (node (ref "R4") (pin "1") (pinfunction "1_1") (pintype "passive"))
      (node (ref "R5") (pin "1") (pinfunction "1_1") (pintype "passive"))
      (node (ref "RST1") (pin "2") (pinfunction "2_2") (pintype "passive"))
      (node (ref "RST2") (pin "2") (pinfunction "2_2") (pintype "passive"))
      (node (ref "U1") (pin "23") (pinfunction "VSS_1_23") (pintype "passive"))
      (node (ref "U1") (pin "35") (pinfunction "VSS_2_35") (pintype "passive"))
      (node (ref "U1") (pin "47") (pinfunction "VSS_3_47") (pintype "passive"))
      (node (ref "U1") (pin "8") (pinfunction "VSSA_8") (pintype "passive"))
      (node (ref "U2") (pin "2") (pinfunction "GND_2") (pintype "passive"))
      (node (ref "U3") (pin "2") (pinfunction "GND_2") (pintype "passive"))
      (node (ref "U4") (pin "10") (pinfunction "INPB_10") (pintype "passive"))
      (node (ref "U4") (pin "14") (pinfunction "XI_14") (pintype "passive"))
      (node (ref "U4") (pin "15") (pinfunction "RATE_15") (pintype "passive"))
      (node (ref "U4") (pin "5") (pinfunction "AGND_5") (pintype "passive"))
      (node (ref "U4") (pin "9") (pinfunction "INNB_9") (pintype "passive"))
      (node (ref "U5") (pin "1") (pinfunction "VSSIO0_1") (pintype "passive"))
      (node (ref "U5") (pin "12") (pinfunction "VSSPP_12") (pintype "passive"))
      (node (ref "U5") (pin "16") (pinfunction "VSS_16") (pintype "passive"))
      (node (ref "U5") (pin "17") (pinfunction "VSSIO2_17") (pintype "passive"))
      (node (ref "U5") (pin "18") (pinfunction "CVSS_18") (pintype "passive"))
      (node (ref "U5") (pin "23") (pinfunction "VSSA_23") (pintype "passive"))
      (node (ref "U5") (pin "3") (pinfunction "VSSIO0_3") (pintype "passive"))
      (node (ref "U5") (pin "7") (pinfunction "VSSIO1_7") (pintype "passive"))
      (node (ref "U5") (pin "8") (pinfunction "VSSPP_8") (pintype "passive"))
      (node (ref "U6") (pin "1") (pinfunction "GND_1") (pintype "passive"))
      (node (ref "U7") (pin "4") (pinfunction "GND_4") (pintype "passive"))
      (node (ref "U8") (pin "19") (pinfunction "PGND_19") (pintype "passive"))
      (node (ref "U8") (pin "24") (pinfunction "PGND_24") (pintype "passive"))
      (node (ref "U8") (pin "29") (pinfunction "GND_29") (pintype "passive"))
      (node (ref "U8") (pin "3") (pinfunction "LINP_3") (pintype "passive"))
      (node (ref "U8") (pin "4") (pinfunction "LINN_4") (pintype "passive"))
      (node (ref "U8") (pin "8") (pinfunction "AGND_8") (pintype "passive"))
      (node (ref "X1") (pin "2") (pinfunction "GND_2") (pintype "passive"))
      (node (ref "X2") (pin "2") (pinfunction "GND_2") (pintype "passive"))
    )
    (net (code "35") (name "Net-(C31-Pad1)") (class "Default")
      (node (ref "C31") (pin "1") (pinfunction "1_1") (pintype "passive"))
      (node (ref "U8") (pin "26") (pinfunction "BSN_26") (pintype "passive"))
    )
    (net (code "36") (name "Net-(C33-Pad1)") (class "Default")
      (node (ref "C33") (pin "1") (pinfunction "1_1") (pintype "passive"))
      (node (ref "U8") (pin "22") (pinfunction "BSN_22") (pintype "passive"))
    )
    (net (code "37") (name "Net-(C36-Pad1)") (class "Default")
      (node (ref "C36") (pin "1") (pinfunction "1_1") (pintype "passive"))
      (node (ref "U8") (pin "21") (pinfunction "BSP_21") (pintype "passive"))
    )
    (net (code "38") (name "Net-(C37-Pad1)") (class "Default")
      (node (ref "C37") (pin "1") (pinfunction "1_1") (pintype "passive"))
      (node (ref "U8") (pin "17") (pinfunction "BSP_17") (pintype "passive"))
    )
    (net (code "39") (name "Net-(D2-Pad1)") (class "Default")
      (node (ref "D2") (pin "1") (pinfunction "1_1") (pintype "passive"))
      (node (ref "R3") (pin "1") (pinfunction "1_1") (pintype "passive"))
    )
    (net (code "40") (name "Net-(P2-Pad1)") (class "Default")
      (node (ref "P2") (pin "1") (pinfunction "1_1") (pintype "passive"))
      (node (ref "R13") (pin "1") (pinfunction "1_1") (pintype "passive"))
    )
    (net (code "41") (name "Net-(P2-Pad2)") (class "Default")
      (node (ref "P2") (pin "2") (pinfunction "2_2") (pintype "passive"))
      (node (ref "R12") (pin "1") (pinfunction "1_1") (pintype "passive"))
    )
    (net (code "42") (name "Net-(Q1-B)") (class "Default")
      (node (ref "Q1") (pin "1") (pinfunction "B_1") (pintype "passive"))
      (node (ref "U4") (pin "2") (pinfunction "BASE_2") (pintype "passive"))
    )
    (net (code "43") (name "Net-(Q1-C)") (class "Default")
      (node (ref "C20") (pin "2") (pinfunction "2_2") (pintype "passive"))
      (node (ref "P2") (pin "4") (pinfunction "4_4") (pintype "passive"))
      (node (ref "Q1") (pin "3") (pinfunction "C_3") (pintype "passive"))
      (node (ref "R10") (pin "2") (pinfunction "2_2") (pintype "passive"))
      (node (ref "U4") (pin "3") (pinfunction "AVDD_3") (pintype "passive"))
    )
    (net (code "44") (name "Net-(Q2-B)") (class "Default")
      (node (ref "Q2") (pin "1") (pinfunction "B_1") (pintype "passive"))
      (node (ref "R9") (pin "1") (pinfunction "1_1") (pintype "passive"))
    )
    (net (code "45") (name "Net-(Q2-C)") (class "Default")
      (node (ref "Q2") (pin "3") (pinfunction "C_3") (pintype "passive"))
      (node (ref "R7") (pin "1") (pinfunction "1_1") (pintype "passive"))
      (node (ref "R8") (pin "2") (pinfunction "2_2") (pintype "passive"))
    )
    (net (code "46") (name "Net-(U1-OSC_IN{slash}PD0)") (class "Default")
      (node (ref "U1") (pin "5") (pinfunction "OSC_IN/PD0_5") (pintype "passive"))
      (node (ref "X1") (pin "1") (pinfunction "OSC1_1") (pintype "passive"))
    )
    (net (code "47") (name "Net-(U1-OSC_OUT{slash}PD1)") (class "Default")
      (node (ref "U1") (pin "6") (pinfunction "OSC_OUT/PD1_6") (pintype "passive"))
      (node (ref "X1") (pin "3") (pinfunction "OSC2_3") (pintype "passive"))
    )
    (net (code "48") (name "Net-(U2-BST)") (class "Default")
      (node (ref "C1") (pin "2") (pinfunction "2_2") (pintype "passive"))
      (node (ref "U2") (pin "1") (pinfunction "BST_1") (pintype "passive"))
    )
    (net (code "49") (name "Net-(U2-EN)") (class "Default")
      (node (ref "R1") (pin "1") (pinfunction "1_1") (pintype "passive"))
      (node (ref "R4") (pin "2") (pinfunction "2_2") (pintype "passive"))
      (node (ref "U2") (pin "4") (pinfunction "EN_4") (pintype "passive"))
    )
    (net (code "50") (name "Net-(U2-FB)") (class "Default")
      (node (ref "C4") (pin "1") (pinfunction "1_1") (pintype "passive"))
      (node (ref "R2") (pin "1") (pinfunction "1_1") (pintype "passive"))
      (node (ref "R5") (pin "2") (pinfunction "2_2") (pintype "passive"))
      (node (ref "U2") (pin "3") (pinfunction "FB_3") (pintype "passive"))
    )
    (net (code "51") (name "Net-(U2-SW)") (class "Default")
      (node (ref "C1") (pin "1") (pinfunction "1_1") (pintype "passive"))
      (node (ref "D1") (pin "2") (pinfunction "2_2") (pintype "passive"))
      (node (ref "L1") (pin "1") (pinfunction "1_1") (pintype "passive"))
      (node (ref "U2") (pin "6") (pinfunction "SW_6") (pintype "passive"))
    )
    (net (code "52") (name "Net-(U3-NC)") (class "Default")
      (node (ref "C11") (pin "1") (pinfunction "1_1") (pintype "passive"))
      (node (ref "U3") (pin "4") (pinfunction "NC_4") (pintype "passive"))
    )
    (net (code "53") (name "Net-(U4-INNA)") (class "Default")
      (node (ref "C23") (pin "1") (pinfunction "1_1") (pintype "passive"))
      (node (ref "R12") (pin "2") (pinfunction "2_2") (pintype "passive"))
      (node (ref "U4") (pin "7") (pinfunction "INNA_7") (pintype "passive"))
    )
    (net (code "54") (name "Net-(U4-INPA)") (class "Default")
      (node (ref "C23") (pin "2") (pinfunction "2_2") (pintype "passive"))
      (node (ref "R13") (pin "2") (pinfunction "2_2") (pintype "passive"))
      (node (ref "U4") (pin "8") (pinfunction "INPA_8") (pintype "passive"))
    )
    (net (code "55") (name "Net-(U4-VBG)") (class "Default")
      (node (ref "C21") (pin "1") (pinfunction "1_1") (pintype "passive"))
      (node (ref "U4") (pin "6") (pinfunction "VBG_6") (pintype "passive"))
    )
    (net (code "56") (name "Net-(U4-VFB)") (class "Default")
      (node (ref "R10") (pin "1") (pinfunction "1_1") (pintype "passive"))
      (node (ref "R11") (pin "2") (pinfunction "2_2") (pintype "passive"))
      (node (ref "U4") (pin "4") (pinfunction "VFB_4") (pintype "passive"))
    )
    (net (code "57") (name "Net-(U5-RES)") (class "Default")
      (node (ref "R14") (pin "2") (pinfunction "2_2") (pintype "passive"))
      (node (ref "U5") (pin "5") (pinfunction "RES_5") (pintype "passive"))
    )
    (net (code "58") (name "Net-(U5-RXD)") (class "Default")
      (node (ref "R8") (pin "1") (pinfunction "1_1") (pintype "passive"))
      (node (ref "U5") (pin "28") (pinfunction "RXD_28") (pintype "passive"))
    )
    (net (code "59") (name "Net-(U5-XIN)") (class "Default")
      (node (ref "U5") (pin "24") (pinfunction "XIN_24") (pintype "passive"))
      (node (ref "X2") (pin "1") (pinfunction "OSC1_1") (pintype "passive"))
    )
    (net (code "60") (name "Net-(U5-XOUT)") (class "Default")
      (node (ref "U5") (pin "25") (pinfunction "XOUT_25") (pintype "passive"))
      (node (ref "X2") (pin "3") (pinfunction "OSC2_3") (pintype "passive"))
    )
    (net (code "61") (name "Net-(U8-GVDD)") (class "Default")
      (node (ref "C42") (pin "2") (pinfunction "2_2") (pintype "passive"))
      (node (ref "U8") (pin "10") (pinfunction "PLIMIT_10") (pintype "passive"))
      (node (ref "U8") (pin "9") (pinfunction "GVDD_9") (pintype "passive"))
    )
    (net (code "62") (name "Net-(U8-RINN)") (class "Default")
      (node (ref "C38") (pin "1") (pinfunction "1_1") (pintype "passive"))
      (node (ref "U8") (pin "11") (pinfunction "RINN_11") (pintype "passive"))
    )
    (net (code "63") (name "Net-(U8-RINP)") (class "Default")
      (node (ref "C39") (pin "1") (pinfunction "1_1") (pintype "passive"))
      (node (ref "U8") (pin "12") (pinfunction "RINP_12") (pintype "passive"))
    )
    (net (code "64") (name "VCC") (class "Default")
      (node (ref "C10") (pin "2") (pinfunction "2_2") (pintype "passive"))
      (node (ref "C18") (pin "2") (pinfunction "2_2") (pintype "passive"))
      (node (ref "C19") (pin "1") (pinfunction "1_1") (pintype "passive"))
      (node (ref "C22") (pin "1") (pinfunction "1_1") (pintype "passive"))
      (node (ref "C24") (pin "1") (pinfunction "1_1") (pintype "passive"))
      (node (ref "C35") (pin "1") (pinfunction "1_1") (pintype "passive"))
      (node (ref "C4") (pin "2") (pinfunction "2_2") (pintype "passive"))
      (node (ref "C40") (pin "1") (pinfunction "1_1") (pintype "passive"))
      (node (ref "C41") (pin "1") (pinfunction "1_1") (pintype "passive"))
      (node (ref "C43") (pin "1") (pinfunction "1_1") (pintype "passive"))
      (node (ref "C44") (pin "1") (pinfunction "1_1") (pintype "passive"))
      (node (ref "C5") (pin "2") (pinfunction "2_2") (pintype "passive"))
      (node (ref "C6") (pin "2") (pinfunction "2_2") (pintype "passive"))
      (node (ref "C9") (pin "2") (pinfunction "2_2") (pintype "passive"))
      (node (ref "L1") (pin "2") (pinfunction "2_2") (pintype "passive"))
      (node (ref "P1") (pin "3") (pinfunction "3_3") (pintype "passive"))
      (node (ref "P3") (pin "5") (pinfunction "5_5") (pintype "passive"))
      (node (ref "Q1") (pin "2") (pinfunction "E_2") (pintype "passive"))
      (node (ref "R14") (pin "1") (pinfunction "1_1") (pintype "passive"))
      (node (ref "R16") (pin "1") (pinfunction "1_1") (pintype "passive"))
      (node (ref "R2") (pin "2") (pinfunction "2_2") (pintype "passive"))
      (node (ref "R3") (pin "2") (pinfunction "2_2") (pintype "passive"))
      (node (ref "R7") (pin "2") (pinfunction "2_2") (pintype "passive"))
      (node (ref "U3") (pin "1") (pinfunction "IN_1") (pintype "passive"))
      (node (ref "U3") (pin "3") (pinfunction "EN_3") (pintype "passive"))
      (node (ref "U4") (pin "1") (pinfunction "VSUP_1") (pintype "passive"))
      (node (ref "U4") (pin "16") (pinfunction "DVDD_16") (pintype "passive"))
      (node (ref "U5") (pin "10") (pinfunction "VDDPP_10") (pintype "passive"))
      (node (ref "U5") (pin "2") (pinfunction "VDDIO0_2") (pintype "passive"))
      (node (ref "U5") (pin "20") (pinfunction "VDDIO2_20") (pintype "passive"))
      (node (ref "U5") (pin "26") (pinfunction "VDDA_26") (pintype "passive"))
      (node (ref "U5") (pin "6") (pinfunction "VDDIO1_6") (pintype "passive"))
      (node (ref "U7") (pin "10") (pinfunction "VDD_10") (pintype "passive"))
    )
    (net (code "65") (name "VCC_3V3_MCU") (class "Default")
      (node (ref "C13") (pin "1") (pinfunction "1_1") (pintype "passive"))
      (node (ref "C14") (pin "1") (pinfunction "1_1") (pintype "passive"))
      (node (ref "C15") (pin "1") (pinfunction "1_1") (pintype "passive"))
      (node (ref "C16") (pin "1") (pinfunction "1_1") (pintype "passive"))
      (node (ref "C17") (pin "1") (pinfunction "1_1") (pintype "passive"))
      (node (ref "C7") (pin "1") (pinfunction "1_1") (pintype "passive"))
      (node (ref "C8") (pin "2") (pinfunction "2_2") (pintype "passive"))
      (node (ref "R6") (pin "1") (pinfunction "1_1") (pintype "passive"))
      (node (ref "U1") (pin "1") (pinfunction "VBAT_1") (pintype "passive"))
      (node (ref "U1") (pin "24") (pinfunction "VDD_1_24") (pintype "passive"))
      (node (ref "U1") (pin "36") (pinfunction "VDD_2_36") (pintype "passive"))
      (node (ref "U1") (pin "48") (pinfunction "VDD_3_48") (pintype "passive"))
      (node (ref "U1") (pin "9") (pinfunction "VDDA_9") (pintype "passive"))
      (node (ref "U3") (pin "5") (pinfunction "OUT_5") (pintype "passive"))
      (node (ref "U6") (pin "2") (pinfunction "VCC_2") (pintype "passive"))
    )
    (net (code "66") (name "VCC_12V") (class "Default")
      (node (ref "C2") (pin "2") (pinfunction "2_2") (pintype "passive"))
      (node (ref "C25") (pin "1") (pinfunction "1_1") (pintype "passive"))
      (node (ref "C26") (pin "1") (pinfunction "1_1") (pintype "passive"))
      (node (ref "C27") (pin "1") (pinfunction "1_1") (pintype "passive"))
      (node (ref "C28") (pin "1") (pinfunction "1_1") (pintype "passive"))
      (node (ref "C29") (pin "2") (pinfunction "2_2") (pintype "passive"))
      (node (ref "C3") (pin "2") (pinfunction "2_2") (pintype "passive"))
      (node (ref "P1") (pin "8") (pinfunction "8_8") (pintype "passive"))
      (node (ref "R1") (pin "2") (pinfunction "2_2") (pintype "passive"))
      (node (ref "R15") (pin "2") (pinfunction "2_2") (pintype "passive"))
      (node (ref "U2") (pin "5") (pinfunction "VIN_5") (pintype "passive"))
      (node (ref "U8") (pin "15") (pinfunction "PVCC_15") (pintype "passive"))
      (node (ref "U8") (pin "16") (pinfunction "PVCC_16") (pintype "passive"))
      (node (ref "U8") (pin "27") (pinfunction "PVCC_27") (pintype "passive"))
      (node (ref "U8") (pin "28") (pinfunction "PVCC_28") (pintype "passive"))
      (node (ref "U8") (pin "7") (pinfunction "AVCC_7") (pintype "passive"))
    )
    (net (code "67") (name "unconnected-(U1-BOOT0-Pad44)") (class "Default")
      (node (ref "U1") (pin "44") (pinfunction "BOOT0_44") (pintype "passive"))
    )
    (net (code "68") (name "unconnected-(U1-PA0{slash}WKUP{slash}USART_~{CTS}{slash}ADC0{slash}TIM2_CH1_ETR-Pad10)") (class "Default")
      (node (ref "U1") (pin "10") (pinfunction "PA0/WKUP/USART_~{CTS}/ADC0/TIM2_CH1_ETR_10") (pintype "passive"))
    )
    (net (code "69") (name "unconnected-(U1-PA1{slash}USART2_~{RTS}{slash}ADC1{slash}TIM2_CH2-Pad11)") (class "Default")
      (node (ref "U1") (pin "11") (pinfunction "PA1/USART2_~{RTS}/ADC1/TIM2_CH2_11") (pintype "passive"))
    )
    (net (code "70") (name "unconnected-(U1-PA5{slash}SPI1_SCLK{slash}ADC5-Pad15)") (class "Default")
      (node (ref "U1") (pin "15") (pinfunction "PA5/SPI1_SCLK/ADC5_15") (pintype "passive"))
    )
    (net (code "71") (name "unconnected-(U1-PA6{slash}SPI1_MISO{slash}ADC6{slash}TIM3_CH1-Pad16)") (class "Default")
      (node (ref "U1") (pin "16") (pinfunction "PA6/SPI1_MISO/ADC6/TIM3_CH1_16") (pintype "passive"))
    )
    (net (code "72") (name "unconnected-(U1-PA7{slash}SPI1_MOSI{slash}ADC7{slash}TIM3_CH2-Pad17)") (class "Default")
      (node (ref "U1") (pin "17") (pinfunction "PA7/SPI1_MOSI/ADC7/TIM3_CH2_17") (pintype "passive"))
    )
    (net (code "73") (name "unconnected-(U1-PA8{slash}USART1_CK{slash}TIM1_CH1{slash}MCO-Pad29)") (class "Default")
      (node (ref "U1") (pin "29") (pinfunction "PA8/USART1_CK/TIM1_CH1/MCO_29") (pintype "passive"))
    )
    (net (code "74") (name "unconnected-(U1-PA11{slash}USART1_~{CTS}{slash}CANRx{slash}USBDM{slash}TIM1_CH4-Pad32)") (class "Default")
      (node (ref "U1") (pin "32") (pinfunction "PA11/USART1_~{CTS}/CANRx/USBDM/TIM1_CH4_32") (pintype "passive"))
    )
    (net (code "75") (name "unconnected-(U1-PA12{slash}USART1_~{RTS}{slash}CANTx{slash}USBDP{slash}TIM1_ETR-Pad33)") (class "Default")
      (node (ref "U1") (pin "33") (pinfunction "PA12/USART1_~{RTS}/CANTx/USBDP/TIM1_ETR_33") (pintype "passive"))
    )
    (net (code "76") (name "unconnected-(U1-PA15{slash}JTDI-Pad38)") (class "Default")
      (node (ref "U1") (pin "38") (pinfunction "PA15/JTDI_38") (pintype "passive"))
    )
    (net (code "77") (name "unconnected-(U1-PB0{slash}ADC8{slash}TIM3_CH3-Pad18)") (class "Default")
      (node (ref "U1") (pin "18") (pinfunction "PB0/ADC8/TIM3_CH3_18") (pintype "passive"))
    )
    (net (code "78") (name "unconnected-(U1-PB1{slash}ADC9{slash}TIM3_CH4-Pad19)") (class "Default")
      (node (ref "U1") (pin "19") (pinfunction "PB1/ADC9/TIM3_CH4_19") (pintype "passive"))
    )
    (net (code "79") (name "unconnected-(U1-PB2{slash}BOOT1-Pad20)") (class "Default")
      (node (ref "U1") (pin "20") (pinfunction "PB2/BOOT1_20") (pintype "passive"))
    )
    (net (code "80") (name "unconnected-(U1-PB3{slash}JTDO-Pad39)") (class "Default")
      (node (ref "U1") (pin "39") (pinfunction "PB3/JTDO_39") (pintype "passive"))
    )
    (net (code "81") (name "unconnected-(U1-PB4{slash}JNTRST-Pad40)") (class "Default")
      (node (ref "U1") (pin "40") (pinfunction "PB4/JNTRST_40") (pintype "passive"))
    )
    (net (code "82") (name "unconnected-(U1-PB5{slash}II21_SMBAI-Pad41)") (class "Default")
      (node (ref "U1") (pin "41") (pinfunction "PB5/II21_SMBAI_41") (pintype "passive"))
    )
    (net (code "83") (name "unconnected-(U1-PB8{slash}TIM4_CH3-Pad45)") (class "Default")
      (node (ref "U1") (pin "45") (pinfunction "PB8/TIM4_CH3_45") (pintype "passive"))
    )
    (net (code "84") (name "unconnected-(U1-PB9{slash}TIM4_CH4-Pad46)") (class "Default")
      (node (ref "U1") (pin "46") (pinfunction "PB9/TIM4_CH4_46") (pintype "passive"))
    )
    (net (code "85") (name "unconnected-(U1-PB12{slash}SPI2_~{NSS}{slash}IIC2_SMBAI{slash}USART3_CK{slash}TIM1_BKIN-Pad25)") (class "Default")
      (node (ref "U1") (pin "25") (pinfunction "PB12/SPI2_~{NSS}/IIC2_SMBAI/USART3_CK/TIM1_BKIN_25") (pintype "passive"))
    )
    (net (code "86") (name "unconnected-(U1-PB13{slash}SPI2_SCK{slash}USART3_~{CTS}{slash}TIM1_CH1N-Pad26)") (class "Default")
      (node (ref "U1") (pin "26") (pinfunction "PB13/SPI2_SCK/USART3_~{CTS}/TIM1_CH1N_26") (pintype "passive"))
    )
    (net (code "87") (name "unconnected-(U1-PC13{slash}TAMPER{slash}RTC-Pad2)") (class "Default")
      (node (ref "U1") (pin "2") (pinfunction "PC13/TAMPER/RTC_2") (pintype "passive"))
    )
    (net (code "88") (name "unconnected-(U1-PC14{slash}OSC32_IN-Pad3)") (class "Default")
      (node (ref "U1") (pin "3") (pinfunction "PC14/OSC32_IN_3") (pintype "passive"))
    )
    (net (code "89") (name "unconnected-(U1-PC15{slash}OSC32_OUT-Pad4)") (class "Default")
      (node (ref "U1") (pin "4") (pinfunction "PC15/OSC32_OUT_4") (pintype "passive"))
    )
    (net (code "90") (name "unconnected-(U4-XO-Pad13)") (class "Default")
      (node (ref "U4") (pin "13") (pinfunction "XO_13") (pintype "passive"))
    )
    (net (code "91") (name "unconnected-(U5-NC-Pad13)") (class "Default")
      (node (ref "U5") (pin "13") (pinfunction "NC_13") (pintype "passive"))
    )
    (net (code "92") (name "unconnected-(U5-NC-Pad14)") (class "Default")
      (node (ref "U5") (pin "14") (pinfunction "NC_14") (pintype "passive"))
    )
    (net (code "93") (name "unconnected-(U5-NC-Pad15)") (class "Default")
      (node (ref "U5") (pin "15") (pinfunction "NC_15") (pintype "passive"))
    )
    (net (code "94") (name "unconnected-(U6-NC-Pad5)") (class "Default")
      (node (ref "U6") (pin "5") (pinfunction "NC_5") (pintype "passive"))
    )
    (net (code "95") (name "unconnected-(U6-NC-Pad6)") (class "Default")
      (node (ref "U6") (pin "6") (pinfunction "NC_6") (pintype "passive"))
    )
    (net (code "96") (name "unconnected-(U6-NC-Pad7)") (class "Default")
      (node (ref "U6") (pin "7") (pinfunction "NC_7") (pintype "passive"))
    )
    (net (code "97") (name "unconnected-(U6-NC-Pad8)") (class "Default")
      (node (ref "U6") (pin "8") (pinfunction "NC_8") (pintype "passive"))
    )
    (net (code "98") (name "unconnected-(U6-NC-Pad13)") (class "Default")
      (node (ref "U6") (pin "13") (pinfunction "NC_13") (pintype "passive"))
    )
    (net (code "99") (name "unconnected-(U6-NC-Pad14)") (class "Default")
      (node (ref "U6") (pin "14") (pinfunction "NC_14") (pintype "passive"))
    )
    (net (code "100") (name "unconnected-(U6-NC-Pad15)") (class "Default")
      (node (ref "U6") (pin "15") (pinfunction "NC_15") (pintype "passive"))
    )
    (net (code "101") (name "unconnected-(U6-PB1-Pad9)") (class "Default")
      (node (ref "U6") (pin "9") (pinfunction "PB1_9") (pintype "passive"))
    )
    (net (code "102") (name "unconnected-(U6-PB2-Pad10)") (class "Default")
      (node (ref "U6") (pin "10") (pinfunction "PB2_10") (pintype "passive"))
    )
    (net (code "103") (name "unconnected-(U6-PB3-Pad11)") (class "Default")
      (node (ref "U6") (pin "11") (pinfunction "PB3_11") (pintype "passive"))
    )
    (net (code "104") (name "unconnected-(U6-PB4-Pad12)") (class "Default")
      (node (ref "U6") (pin "12") (pinfunction "PB4_12") (pintype "passive"))
    )
    (net (code "105") (name "unconnected-(U6-RST-Pad16)") (class "Default")
      (node (ref "U6") (pin "16") (pinfunction "RST_16") (pintype "passive"))
    )
    (net (code "106") (name "unconnected-(U8-NC-Pad13)") (class "Default")
      (node (ref "U8") (pin "13") (pinfunction "NC_13") (pintype "passive"))
    )
  )
)
